# laser_buck_converter.net
KiCad netlist of a schematic drawn in EAGLE
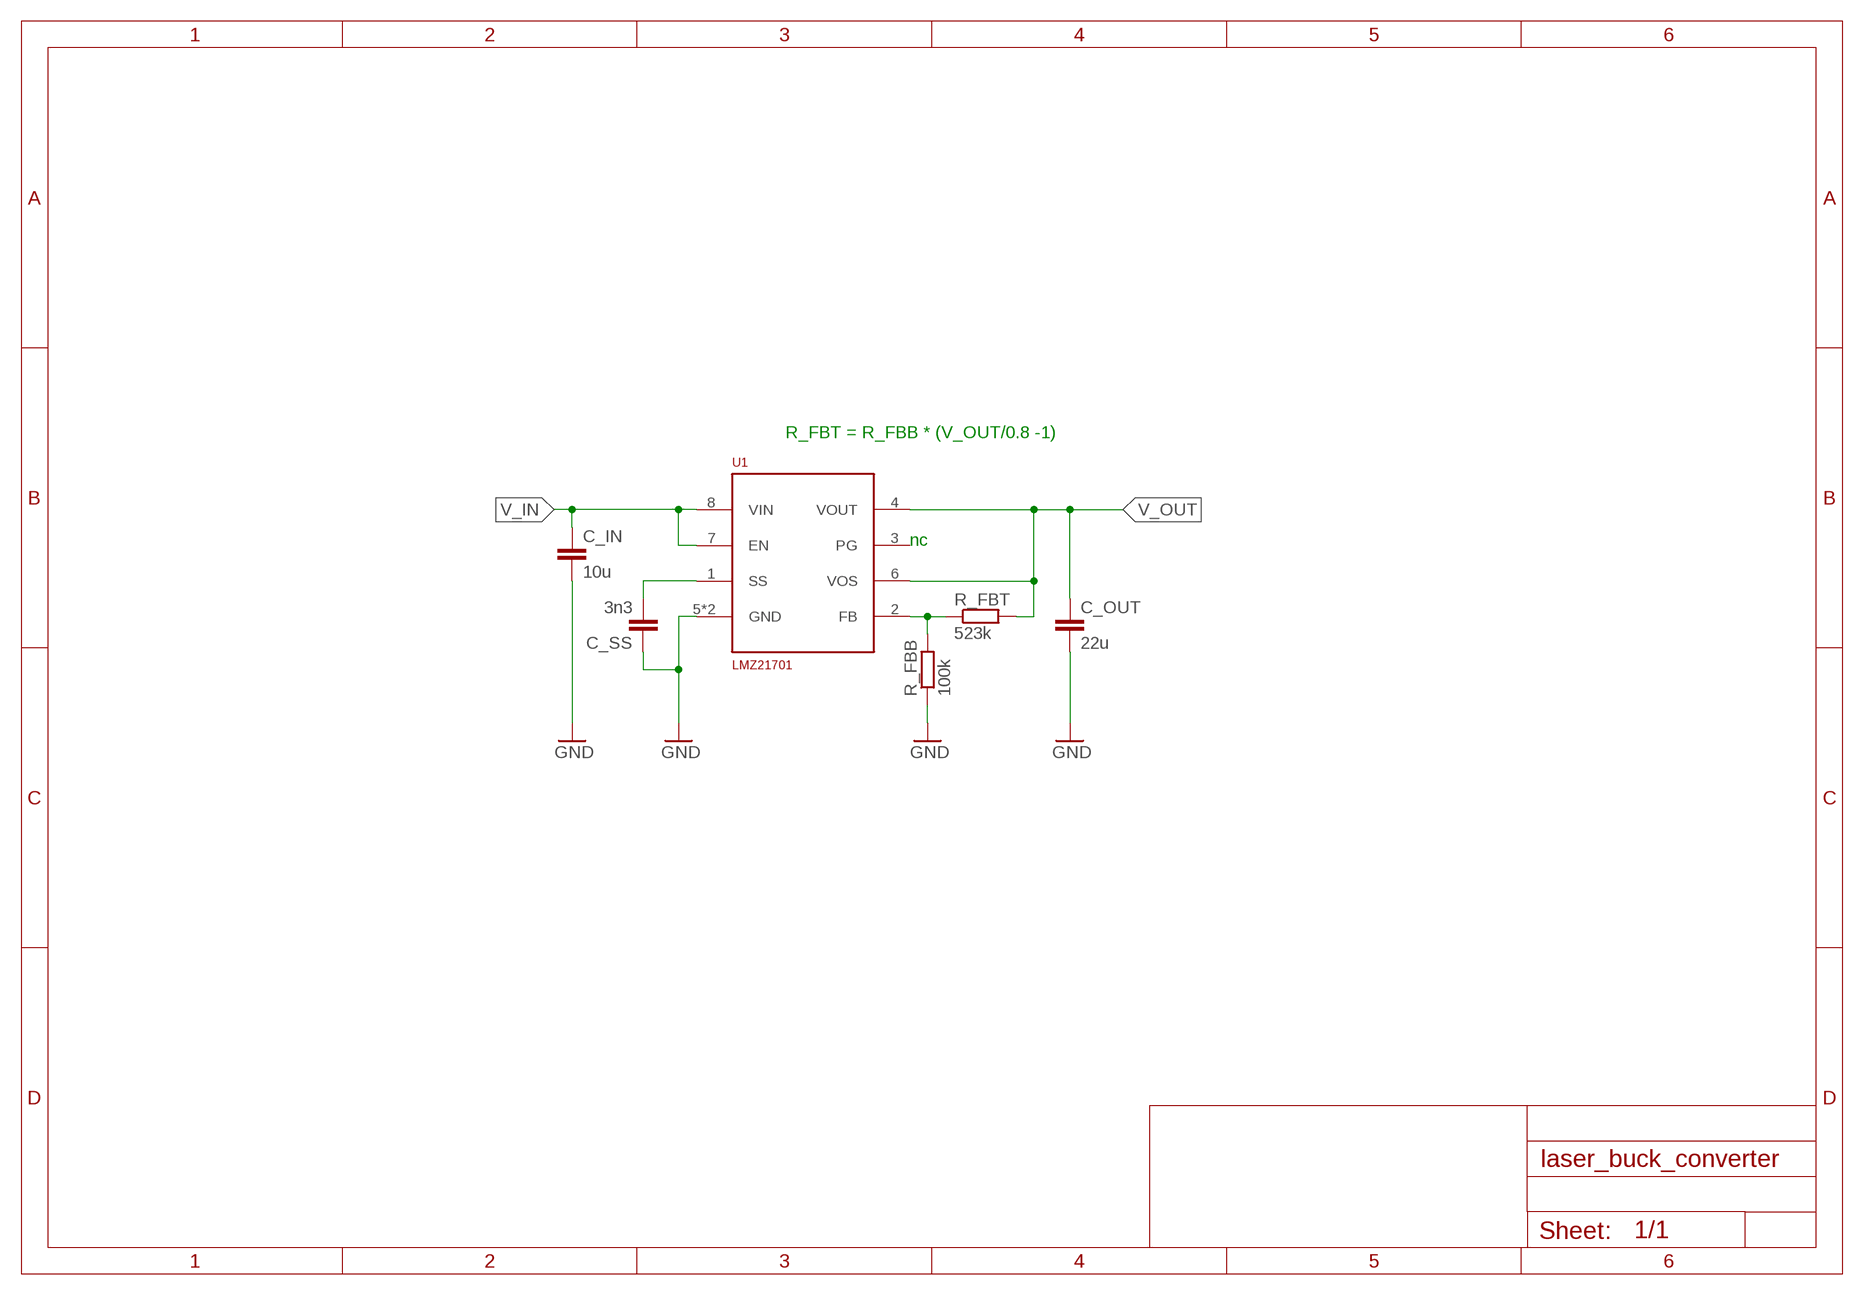
[diagram p0: schematic, sheet 1]

(export (version "E")
  (design (tool "Eeschema 10.0.6"))
  (components
    (comp (ref "C_IN")
      (value "10u")
      (footprint "eagle-import:C0603")
      (libsource (lib "eagle-import") (part "C-EUC0603"))
    )
    (comp (ref "C_OUT")
      (value "22u")
      (footprint "eagle-import:C0603")
      (libsource (lib "eagle-import") (part "C-EUC0603"))
    )
    (comp (ref "C_SS")
      (value "3n3")
      (footprint "eagle-import:C0402")
      (libsource (lib "eagle-import") (part "C-EUC0402"))
    )
    (comp (ref "R_FBB")
      (value "100k")
      (footprint "eagle-import:R0402")
      (libsource (lib "eagle-import") (part "R-EU_R0402"))
    )
    (comp (ref "R_FBT")
      (value "523k")
      (footprint "eagle-import:R0402")
      (libsource (lib "eagle-import") (part "R-EU_R0402"))
    )
    (comp (ref "U1")
      (value "LMZ21701")
      (footprint "eagle-import:SIL0008E")
      (libsource (lib "eagle-import") (part "LMZ21701"))
    )
  )
  (nets
    (net (code "1") (name "GND") (class "Default")
      (node (ref "C_IN") (pin "2") (pinfunction "2_2") (pintype "passive"))
      (node (ref "C_OUT") (pin "2") (pinfunction "2_2") (pintype "passive"))
      (node (ref "C_SS") (pin "1") (pinfunction "1_1") (pintype "passive"))
      (node (ref "R_FBB") (pin "1") (pinfunction "1_1") (pintype "passive"))
      (node (ref "U1") (pin "5") (pinfunction "GND_5") (pintype "bidirectional"))
      (node (ref "U1") (pin "PAD") (pinfunction "GND_PAD") (pintype "bidirectional"))
    )
    (net (code "2") (name "Net-(U1-FB)") (class "Default")
      (node (ref "R_FBB") (pin "2") (pinfunction "2_2") (pintype "passive"))
      (node (ref "R_FBT") (pin "1") (pinfunction "1_1") (pintype "passive"))
      (node (ref "U1") (pin "2") (pinfunction "FB_2") (pintype "bidirectional"))
    )
    (net (code "3") (name "Net-(U1-SS)") (class "Default")
      (node (ref "C_SS") (pin "2") (pinfunction "2_2") (pintype "passive"))
      (node (ref "U1") (pin "1") (pinfunction "SS_1") (pintype "bidirectional"))
    )
    (net (code "4") (name "V_IN") (class "Default")
      (node (ref "C_IN") (pin "1") (pinfunction "1_1") (pintype "passive"))
      (node (ref "U1") (pin "7") (pinfunction "EN_7") (pintype "bidirectional"))
      (node (ref "U1") (pin "8") (pinfunction "VIN_8") (pintype "bidirectional"))
    )
    (net (code "5") (name "V_OUT") (class "Default")
      (node (ref "C_OUT") (pin "1") (pinfunction "1_1") (pintype "passive"))
      (node (ref "R_FBT") (pin "2") (pinfunction "2_2") (pintype "passive"))
      (node (ref "U1") (pin "4") (pinfunction "VOUT_4") (pintype "bidirectional"))
      (node (ref "U1") (pin "6") (pinfunction "VOS_6") (pintype "bidirectional"))
    )
    (net (code "6") (name "unconnected-(U1-PG-Pad3)") (class "Default")
      (node (ref "U1") (pin "3") (pinfunction "PG_3") (pintype "bidirectional"))
    )
  )
)
